# IRF9540NS_IRFZ44_P_N_CHAN.net
KiCad netlist of a schematic drawn in Altium Designer
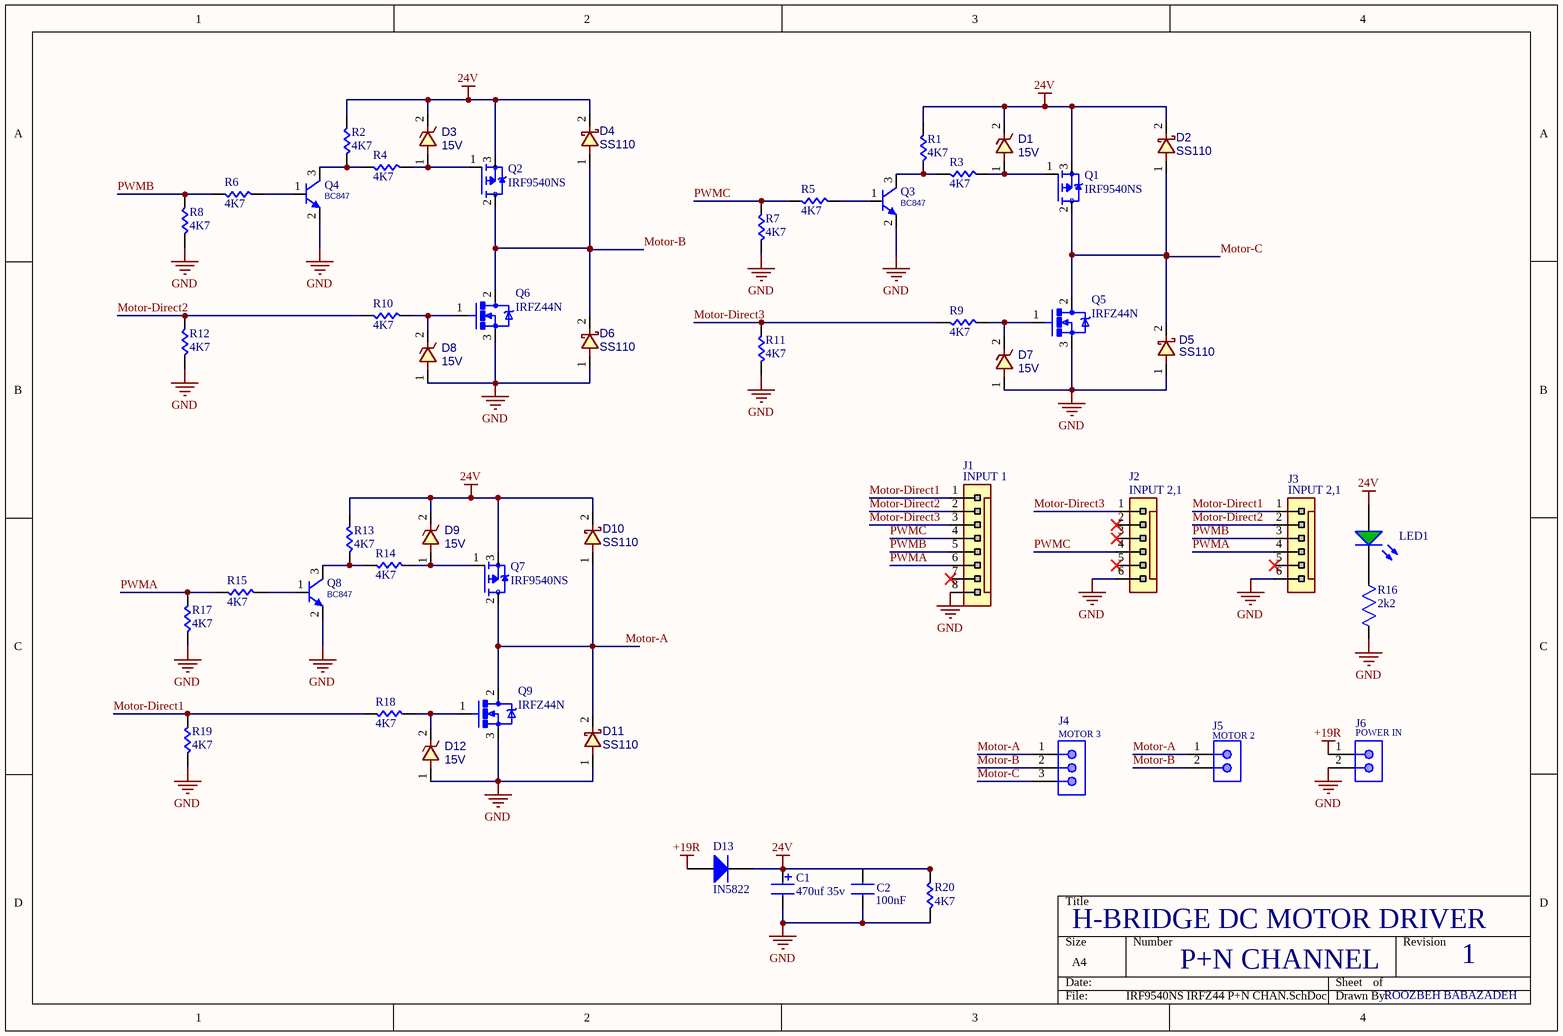
[diagram p0: IRF9540NS IRFZ44 P+N CHAN.SchDoc]

(export (version "E")
  (design (tool "Eeschema 10.0.6"))
  (components
    (comp (ref "C1") (value "470uf 35v") (footprint "C_EL_10X12") (libsource (lib "OTHER") (part "CAP3528")))
    (comp (ref "C2") (value "100nF") (footprint "C0805E") (libsource (lib "OTHER") (part "C")))
    (comp (ref "D1")
      (value "15V")
      (footprint "D_AX02_DO35")
      (description "DIODE, ZENER, 3W, 5.6V")
      (fields (field (name "MANF") "MCC") (field (name "MANF_P#") "3SMAJ5919B-TP"))
      (libsource (lib "diode") (part "ZENER"))
    )
    (comp (ref "D2")
      (value "SS110")
      (footprint "D_SMA")
      (description "DIODE, SCHOTTKY, 40V, 1A")
      (fields (field (name "MANF") "DIODES") (field (name "MANF_P#") "1N5819HW-7-F"))
      (libsource (lib "diode") (part "SCHOTTKY"))
    )
    (comp (ref "D3")
      (value "15V")
      (footprint "D_AX02_DO35")
      (description "DIODE, ZENER, 3W, 5.6V")
      (fields (field (name "MANF") "MCC") (field (name "MANF_P#") "3SMAJ5919B-TP"))
      (libsource (lib "diode") (part "ZENER"))
    )
    (comp (ref "D4")
      (value "SS110")
      (footprint "D_SMA")
      (description "DIODE, SCHOTTKY, 40V, 1A")
      (fields (field (name "MANF") "DIODES") (field (name "MANF_P#") "1N5819HW-7-F"))
      (libsource (lib "diode") (part "SCHOTTKY"))
    )
    (comp (ref "D5")
      (value "SS110")
      (footprint "D_SMA")
      (description "DIODE, SCHOTTKY, 40V, 1A")
      (fields (field (name "MANF") "DIODES") (field (name "MANF_P#") "1N5819HW-7-F"))
      (libsource (lib "diode") (part "SCHOTTKY"))
    )
    (comp (ref "D6")
      (value "SS110")
      (footprint "D_SMA")
      (description "DIODE, SCHOTTKY, 40V, 1A")
      (fields (field (name "MANF") "DIODES") (field (name "MANF_P#") "1N5819HW-7-F"))
      (libsource (lib "diode") (part "SCHOTTKY"))
    )
    (comp (ref "D7")
      (value "15V")
      (footprint "D_AX02_DO35")
      (description "DIODE, ZENER, 3W, 5.6V")
      (fields (field (name "MANF") "MCC") (field (name "MANF_P#") "3SMAJ5919B-TP"))
      (libsource (lib "diode") (part "ZENER"))
    )
    (comp (ref "D8")
      (value "15V")
      (footprint "D_AX02_DO35")
      (description "DIODE, ZENER, 3W, 5.6V")
      (fields (field (name "MANF") "MCC") (field (name "MANF_P#") "3SMAJ5919B-TP"))
      (libsource (lib "diode") (part "ZENER"))
    )
    (comp (ref "D9")
      (value "15V")
      (footprint "D_AX02_DO35")
      (description "DIODE, ZENER, 3W, 5.6V")
      (fields (field (name "MANF") "MCC") (field (name "MANF_P#") "3SMAJ5919B-TP"))
      (libsource (lib "diode") (part "ZENER"))
    )
    (comp (ref "D10")
      (value "SS110")
      (footprint "D_SMA")
      (description "DIODE, SCHOTTKY, 40V, 1A")
      (fields (field (name "MANF") "DIODES") (field (name "MANF_P#") "1N5819HW-7-F"))
      (libsource (lib "diode") (part "SCHOTTKY"))
    )
    (comp (ref "D11")
      (value "SS110")
      (footprint "D_SMA")
      (description "DIODE, SCHOTTKY, 40V, 1A")
      (fields (field (name "MANF") "DIODES") (field (name "MANF_P#") "1N5819HW-7-F"))
      (libsource (lib "diode") (part "SCHOTTKY"))
    )
    (comp (ref "D12")
      (value "15V")
      (footprint "D_AX02_DO35")
      (description "DIODE, ZENER, 3W, 5.6V")
      (fields (field (name "MANF") "MCC") (field (name "MANF_P#") "3SMAJ5919B-TP"))
      (libsource (lib "diode") (part "ZENER"))
    )
    (comp (ref "D13")
      (value "IN5822")
      (footprint "D_AX06_DO27")
      (description "1 Amp General Purpose Rectifier")
      (fields (field (name "PUBLISHER") "Altium Limited"))
      (libsource (lib "Miscellaneous Devices") (part "Diode 1N4005"))
    )
    (comp (ref "J1")
      (value "INPUT 1")
      (footprint "WF_8")
      (description "Header, WF, Pitch: 2.54mm")
      (libsource (lib "xh-xhr-wf-hhdr-hh6r") (part "HDRWF_8"))
    )
    (comp (ref "J2")
      (value "INPUT 2,1")
      (footprint "WF_6")
      (description "Header, WF, Pitch: 2.54mm")
      (libsource (lib "xh-xhr-wf-hhdr-hh6r") (part "HDRWF_6"))
    )
    (comp (ref "J3")
      (value "INPUT 2,1")
      (footprint "WF_6")
      (description "Header, WF, Pitch: 2.54mm")
      (libsource (lib "xh-xhr-wf-hhdr-hh6r") (part "HDRWF_6"))
    )
    (comp (ref "J4")
      (value "MOTOR 3")
      (footprint "PWL_3")
      (description "WR-PHD Pin Header, THT, pitch 2.54mm, Single Row, Vertical, 3pin")
      (fields (field (name "PART NUMBER") "61300311121") (field (name "PUBLISHER") "Wurth Elektronik"))
      (libsource (lib "sip m") (part "sip 3"))
    )
    (comp (ref "J5")
      (value "MOTOR 2")
      (footprint "PWL_2")
      (description "WR-PHD Pin Header, THT, pitch 2.54mm, Single Row, Vertical, 2pin")
      (fields (field (name "PART NUMBER") "61300211121") (field (name "PUBLISHER") "Wurth Elektronik"))
      (libsource (lib "sip m") (part "sip 2"))
    )
    (comp (ref "J6")
      (value "POWER IN")
      (footprint "PWL_2")
      (description "WR-PHD Pin Header, THT, pitch 2.54mm, Single Row, Vertical, 2pin")
      (fields (field (name "PART NUMBER") "61300211121") (field (name "PUBLISHER") "Wurth Elektronik"))
      (libsource (lib "sip m") (part "sip 2"))
    )
    (comp (ref "LED1") (value "~") (footprint "LED1206RED") (libsource (lib "OTHER") (part "LED3mm")))
    (comp (ref "Q1")
      (value "IRF9540NS")
      (footprint "DPAK2")
      (fields (field (name "MP") "IRF9540NSTRLPBF") (field (name "MF") "Infineon"))
      (libsource (lib "IRF9540N") (part "IRF9540NSTRLPBF"))
    )
    (comp (ref "Q2")
      (value "IRF9540NS")
      (footprint "DPAK2")
      (fields (field (name "MP") "IRF9540NSTRLPBF") (field (name "MF") "Infineon"))
      (libsource (lib "IRF9540N") (part "IRF9540NSTRLPBF"))
    )
    (comp (ref "Q3")
      (value "BC847")
      (footprint "SOT23")
      (description "BJT, NPN, 45v, 0.1A, SOT23")
      (fields (field (name "MANF") "NXP"))
      (libsource (lib "transistor_bjt") (part "NPN_BC847_SOT23"))
    )
    (comp (ref "Q4")
      (value "BC847")
      (footprint "SOT23")
      (description "BJT, NPN, 45v, 0.1A, SOT23")
      (fields (field (name "MANF") "NXP"))
      (libsource (lib "transistor_bjt") (part "NPN_BC847_SOT23"))
    )
    (comp (ref "Q5")
      (value "IRFZ44N")
      (footprint "DPAK2")
      (fields (field (name "MP") "IRFZ44NPBF") (field (name "MF") "Infineon"))
      (libsource (lib "IRFZ44NPBF") (part "IRFZ44NPBF"))
    )
    (comp (ref "Q6")
      (value "IRFZ44N")
      (footprint "DPAK2")
      (fields (field (name "MP") "IRFZ44NPBF") (field (name "MF") "Infineon"))
      (libsource (lib "IRFZ44NPBF") (part "IRFZ44NPBF"))
    )
    (comp (ref "Q7")
      (value "IRF9540NS")
      (footprint "DPAK2")
      (fields (field (name "MP") "IRF9540NSTRLPBF") (field (name "MF") "Infineon"))
      (libsource (lib "IRF9540N") (part "IRF9540NSTRLPBF"))
    )
    (comp (ref "Q8")
      (value "BC847")
      (footprint "SOT23")
      (description "BJT, NPN, 45v, 0.1A, SOT23")
      (fields (field (name "MANF") "NXP"))
      (libsource (lib "transistor_bjt") (part "NPN_BC847_SOT23"))
    )
    (comp (ref "Q9")
      (value "IRFZ44N")
      (footprint "DPAK2")
      (fields (field (name "MP") "IRFZ44NPBF") (field (name "MF") "Infineon"))
      (libsource (lib "IRFZ44NPBF") (part "IRFZ44NPBF"))
    )
    (comp (ref "R1") (value "4K7") (footprint "R0805") (libsource (lib "OTHER") (part "R")))
    (comp (ref "R2") (value "4K7") (footprint "R0805") (libsource (lib "OTHER") (part "R")))
    (comp (ref "R3") (value "4K7") (footprint "R0805") (libsource (lib "OTHER") (part "R")))
    (comp (ref "R4") (value "4K7") (footprint "R0805") (libsource (lib "OTHER") (part "R")))
    (comp (ref "R5") (value "4K7") (footprint "R0805") (libsource (lib "OTHER") (part "R")))
    (comp (ref "R6") (value "4K7") (footprint "R0805") (libsource (lib "OTHER") (part "R")))
    (comp (ref "R7") (value "4K7") (footprint "R0805") (libsource (lib "OTHER") (part "R")))
    (comp (ref "R8") (value "4K7") (footprint "R0805") (libsource (lib "OTHER") (part "R")))
    (comp (ref "R9") (value "4K7") (footprint "R0805") (libsource (lib "OTHER") (part "R")))
    (comp (ref "R10") (value "4K7") (footprint "R0805") (libsource (lib "OTHER") (part "R")))
    (comp (ref "R11") (value "4K7") (footprint "R0805") (libsource (lib "OTHER") (part "R")))
    (comp (ref "R12") (value "4K7") (footprint "R0805") (libsource (lib "OTHER") (part "R")))
    (comp (ref "R13") (value "4K7") (footprint "R0805") (libsource (lib "OTHER") (part "R")))
    (comp (ref "R14") (value "4K7") (footprint "R0805") (libsource (lib "OTHER") (part "R")))
    (comp (ref "R15") (value "4K7") (footprint "R0805") (libsource (lib "OTHER") (part "R")))
    (comp (ref "R16") (value "2k2") (footprint "R0805") (libsource (lib "") (part "R_1")))
    (comp (ref "R17") (value "4K7") (footprint "R0805") (libsource (lib "OTHER") (part "R")))
    (comp (ref "R18") (value "4K7") (footprint "R0805") (libsource (lib "OTHER") (part "R")))
    (comp (ref "R19") (value "4K7") (footprint "R0805") (libsource (lib "OTHER") (part "R")))
    (comp (ref "R20") (value "4K7") (footprint "R0805") (libsource (lib "OTHER") (part "R")))
  )
  (nets
    (net (code "1") (name "+19R") (class "Default")
      (node (ref "D13") (pin "1") (pinfunction "A_1") (pintype "passive"))
      (node (ref "J6") (pin "1") (pinfunction "1_1") (pintype "passive"))
    )
    (net (code "2") (name "/Motor-A") (class "Default")
      (node (ref "D10") (pin "1") (pinfunction "1_1") (pintype "passive"))
      (node (ref "D11") (pin "2") (pinfunction "2_2") (pintype "passive"))
      (node (ref "J4") (pin "1") (pinfunction "1_1") (pintype "passive"))
      (node (ref "J5") (pin "1") (pinfunction "1_1") (pintype "passive"))
      (node (ref "Q7") (pin "2") (pinfunction "2_2") (pintype "passive"))
      (node (ref "Q9") (pin "2") (pinfunction "2_2") (pintype "passive"))
    )
    (net (code "3") (name "/Motor-B") (class "Default")
      (node (ref "D4") (pin "1") (pinfunction "1_1") (pintype "passive"))
      (node (ref "D6") (pin "2") (pinfunction "2_2") (pintype "passive"))
      (node (ref "J4") (pin "2") (pinfunction "2_2") (pintype "passive"))
      (node (ref "J5") (pin "2") (pinfunction "2_2") (pintype "passive"))
      (node (ref "Q2") (pin "2") (pinfunction "2_2") (pintype "passive"))
      (node (ref "Q6") (pin "2") (pinfunction "2_2") (pintype "passive"))
    )
    (net (code "4") (name "/Motor-C") (class "Default")
      (node (ref "D2") (pin "1") (pinfunction "1_1") (pintype "passive"))
      (node (ref "D5") (pin "2") (pinfunction "2_2") (pintype "passive"))
      (node (ref "J4") (pin "3") (pinfunction "3_3") (pintype "passive"))
      (node (ref "Q1") (pin "2") (pinfunction "2_2") (pintype "passive"))
      (node (ref "Q5") (pin "2") (pinfunction "2_2") (pintype "passive"))
    )
    (net (code "5") (name "/Motor-Direct1") (class "Default")
      (node (ref "J1") (pin "1") (pinfunction "1_1") (pintype "passive"))
      (node (ref "J3") (pin "1") (pinfunction "1_1") (pintype "passive"))
      (node (ref "R18") (pin "2") (pintype "passive"))
      (node (ref "R19") (pin "1") (pintype "passive"))
    )
    (net (code "6") (name "/Motor-Direct2") (class "Default")
      (node (ref "J1") (pin "2") (pinfunction "2_2") (pintype "passive"))
      (node (ref "J3") (pin "2") (pinfunction "2_2") (pintype "passive"))
      (node (ref "R10") (pin "2") (pintype "passive"))
      (node (ref "R12") (pin "1") (pintype "passive"))
    )
    (net (code "7") (name "/Motor-Direct3") (class "Default")
      (node (ref "J1") (pin "3") (pinfunction "3_3") (pintype "passive"))
      (node (ref "J2") (pin "1") (pinfunction "1_1") (pintype "passive"))
      (node (ref "R11") (pin "1") (pintype "passive"))
      (node (ref "R9") (pin "2") (pintype "passive"))
    )
    (net (code "8") (name "/PWMA") (class "Default")
      (node (ref "J1") (pin "6") (pinfunction "6_6") (pintype "passive"))
      (node (ref "J3") (pin "4") (pinfunction "4_4") (pintype "passive"))
      (node (ref "R15") (pin "1") (pintype "passive"))
      (node (ref "R17") (pin "2") (pintype "passive"))
    )
    (net (code "9") (name "/PWMB") (class "Default")
      (node (ref "J1") (pin "5") (pinfunction "5_5") (pintype "passive"))
      (node (ref "J3") (pin "3") (pinfunction "3_3") (pintype "passive"))
      (node (ref "R6") (pin "1") (pintype "passive"))
      (node (ref "R8") (pin "2") (pintype "passive"))
    )
    (net (code "10") (name "/PWMC") (class "Default")
      (node (ref "J1") (pin "4") (pinfunction "4_4") (pintype "passive"))
      (node (ref "J2") (pin "4") (pinfunction "4_4") (pintype "passive"))
      (node (ref "R5") (pin "1") (pintype "passive"))
      (node (ref "R7") (pin "2") (pintype "passive"))
    )
    (net (code "11") (name "24V") (class "Default")
      (node (ref "C1") (pin "1") (pinfunction "1_1") (pintype "passive"))
      (node (ref "C2") (pin "2") (pintype "passive"))
      (node (ref "D1") (pin "2") (pinfunction "2_2") (pintype "passive"))
      (node (ref "D10") (pin "2") (pinfunction "2_2") (pintype "passive"))
      (node (ref "D13") (pin "2") (pinfunction "K_2") (pintype "passive"))
      (node (ref "D2") (pin "2") (pinfunction "2_2") (pintype "passive"))
      (node (ref "D3") (pin "2") (pinfunction "2_2") (pintype "passive"))
      (node (ref "D4") (pin "2") (pinfunction "2_2") (pintype "passive"))
      (node (ref "D9") (pin "2") (pinfunction "2_2") (pintype "passive"))
      (node (ref "LED1") (pin "1") (pinfunction "A_1") (pintype "passive"))
      (node (ref "Q1") (pin "3") (pinfunction "3_3") (pintype "passive"))
      (node (ref "Q2") (pin "3") (pinfunction "3_3") (pintype "passive"))
      (node (ref "Q7") (pin "3") (pinfunction "3_3") (pintype "passive"))
      (node (ref "R1") (pin "1") (pintype "passive"))
      (node (ref "R13") (pin "1") (pintype "passive"))
      (node (ref "R2") (pin "1") (pintype "passive"))
      (node (ref "R20") (pin "2") (pintype "passive"))
    )
    (net (code "12") (name "GND") (class "Default")
      (node (ref "C1") (pin "2") (pinfunction "2_2") (pintype "passive"))
      (node (ref "C2") (pin "1") (pintype "passive"))
      (node (ref "D11") (pin "1") (pinfunction "1_1") (pintype "passive"))
      (node (ref "D12") (pin "1") (pinfunction "1_1") (pintype "passive"))
      (node (ref "D5") (pin "1") (pinfunction "1_1") (pintype "passive"))
      (node (ref "D6") (pin "1") (pinfunction "1_1") (pintype "passive"))
      (node (ref "D7") (pin "1") (pinfunction "1_1") (pintype "passive"))
      (node (ref "D8") (pin "1") (pinfunction "1_1") (pintype "passive"))
      (node (ref "J1") (pin "8") (pinfunction "8_8") (pintype "passive"))
      (node (ref "J2") (pin "6") (pinfunction "6_6") (pintype "passive"))
      (node (ref "J3") (pin "6") (pinfunction "6_6") (pintype "passive"))
      (node (ref "J6") (pin "2") (pinfunction "2_2") (pintype "passive"))
      (node (ref "Q3") (pin "2") (pinfunction "E_2") (pintype "passive"))
      (node (ref "Q4") (pin "2") (pinfunction "E_2") (pintype "passive"))
      (node (ref "Q5") (pin "3") (pinfunction "3_3") (pintype "passive"))
      (node (ref "Q6") (pin "3") (pinfunction "3_3") (pintype "passive"))
      (node (ref "Q8") (pin "2") (pinfunction "E_2") (pintype "passive"))
      (node (ref "Q9") (pin "3") (pinfunction "3_3") (pintype "passive"))
      (node (ref "R11") (pin "2") (pintype "passive"))
      (node (ref "R12") (pin "2") (pintype "passive"))
      (node (ref "R16") (pin "2") (pintype "passive"))
      (node (ref "R17") (pin "1") (pintype "passive"))
      (node (ref "R19") (pin "2") (pintype "passive"))
      (node (ref "R20") (pin "1") (pintype "passive"))
      (node (ref "R7") (pin "1") (pintype "passive"))
      (node (ref "R8") (pin "1") (pintype "passive"))
    )
    (net (code "13") (name "Net-(D1-Pad1)") (class "Default")
      (node (ref "D1") (pin "1") (pinfunction "1_1") (pintype "passive"))
      (node (ref "Q1") (pin "1") (pinfunction "1_1") (pintype "passive"))
      (node (ref "R3") (pin "1") (pintype "passive"))
    )
    (net (code "14") (name "Net-(D3-Pad1)") (class "Default")
      (node (ref "D3") (pin "1") (pinfunction "1_1") (pintype "passive"))
      (node (ref "Q2") (pin "1") (pinfunction "1_1") (pintype "passive"))
      (node (ref "R4") (pin "1") (pintype "passive"))
    )
    (net (code "15") (name "Net-(D7-Pad2)") (class "Default")
      (node (ref "D7") (pin "2") (pinfunction "2_2") (pintype "passive"))
      (node (ref "Q5") (pin "1") (pinfunction "1_1") (pintype "passive"))
      (node (ref "R9") (pin "1") (pintype "passive"))
    )
    (net (code "16") (name "Net-(D8-Pad2)") (class "Default")
      (node (ref "D8") (pin "2") (pinfunction "2_2") (pintype "passive"))
      (node (ref "Q6") (pin "1") (pinfunction "1_1") (pintype "passive"))
      (node (ref "R10") (pin "1") (pintype "passive"))
    )
    (net (code "17") (name "Net-(D9-Pad1)") (class "Default")
      (node (ref "D9") (pin "1") (pinfunction "1_1") (pintype "passive"))
      (node (ref "Q7") (pin "1") (pinfunction "1_1") (pintype "passive"))
      (node (ref "R14") (pin "1") (pintype "passive"))
    )
    (net (code "18") (name "Net-(D12-Pad2)") (class "Default")
      (node (ref "D12") (pin "2") (pinfunction "2_2") (pintype "passive"))
      (node (ref "Q9") (pin "1") (pinfunction "1_1") (pintype "passive"))
      (node (ref "R18") (pin "1") (pintype "passive"))
    )
    (net (code "19") (name "Net-(LED1-K)") (class "Default")
      (node (ref "LED1") (pin "2") (pinfunction "K_2") (pintype "passive"))
      (node (ref "R16") (pin "1") (pintype "passive"))
    )
    (net (code "20") (name "Net-(Q3-B)") (class "Default")
      (node (ref "Q3") (pin "1") (pinfunction "B_1") (pintype "passive"))
      (node (ref "R5") (pin "2") (pintype "passive"))
    )
    (net (code "21") (name "Net-(Q3-C)") (class "Default")
      (node (ref "Q3") (pin "3") (pinfunction "C_3") (pintype "passive"))
      (node (ref "R1") (pin "2") (pintype "passive"))
      (node (ref "R3") (pin "2") (pintype "passive"))
    )
    (net (code "22") (name "Net-(Q4-B)") (class "Default")
      (node (ref "Q4") (pin "1") (pinfunction "B_1") (pintype "passive"))
      (node (ref "R6") (pin "2") (pintype "passive"))
    )
    (net (code "23") (name "Net-(Q4-C)") (class "Default")
      (node (ref "Q4") (pin "3") (pinfunction "C_3") (pintype "passive"))
      (node (ref "R2") (pin "2") (pintype "passive"))
      (node (ref "R4") (pin "2") (pintype "passive"))
    )
    (net (code "24") (name "Net-(Q8-B)") (class "Default")
      (node (ref "Q8") (pin "1") (pinfunction "B_1") (pintype "passive"))
      (node (ref "R15") (pin "2") (pintype "passive"))
    )
    (net (code "25") (name "Net-(Q8-C)") (class "Default")
      (node (ref "Q8") (pin "3") (pinfunction "C_3") (pintype "passive"))
      (node (ref "R13") (pin "2") (pintype "passive"))
      (node (ref "R14") (pin "2") (pintype "passive"))
    )
    (net (code "26") (name "unconnected-(J1-Pad7)") (class "Default")
      (node (ref "J1") (pin "7") (pinfunction "7_7") (pintype "passive+no_connect"))
    )
    (net (code "27") (name "unconnected-(J2-Pad2)") (class "Default")
      (node (ref "J2") (pin "2") (pinfunction "2_2") (pintype "passive"))
    )
    (net (code "28") (name "unconnected-(J2-Pad3)") (class "Default")
      (node (ref "J2") (pin "3") (pinfunction "3_3") (pintype "passive"))
    )
    (net (code "29") (name "unconnected-(J2-Pad5)") (class "Default")
      (node (ref "J2") (pin "5") (pinfunction "5_5") (pintype "passive"))
    )
    (net (code "30") (name "unconnected-(J3-Pad5)") (class "Default")
      (node (ref "J3") (pin "5") (pinfunction "5_5") (pintype "passive"))
    )
  )
)
